# d_main3.net
KiCad netlist of a schematic drawn in EAGLE
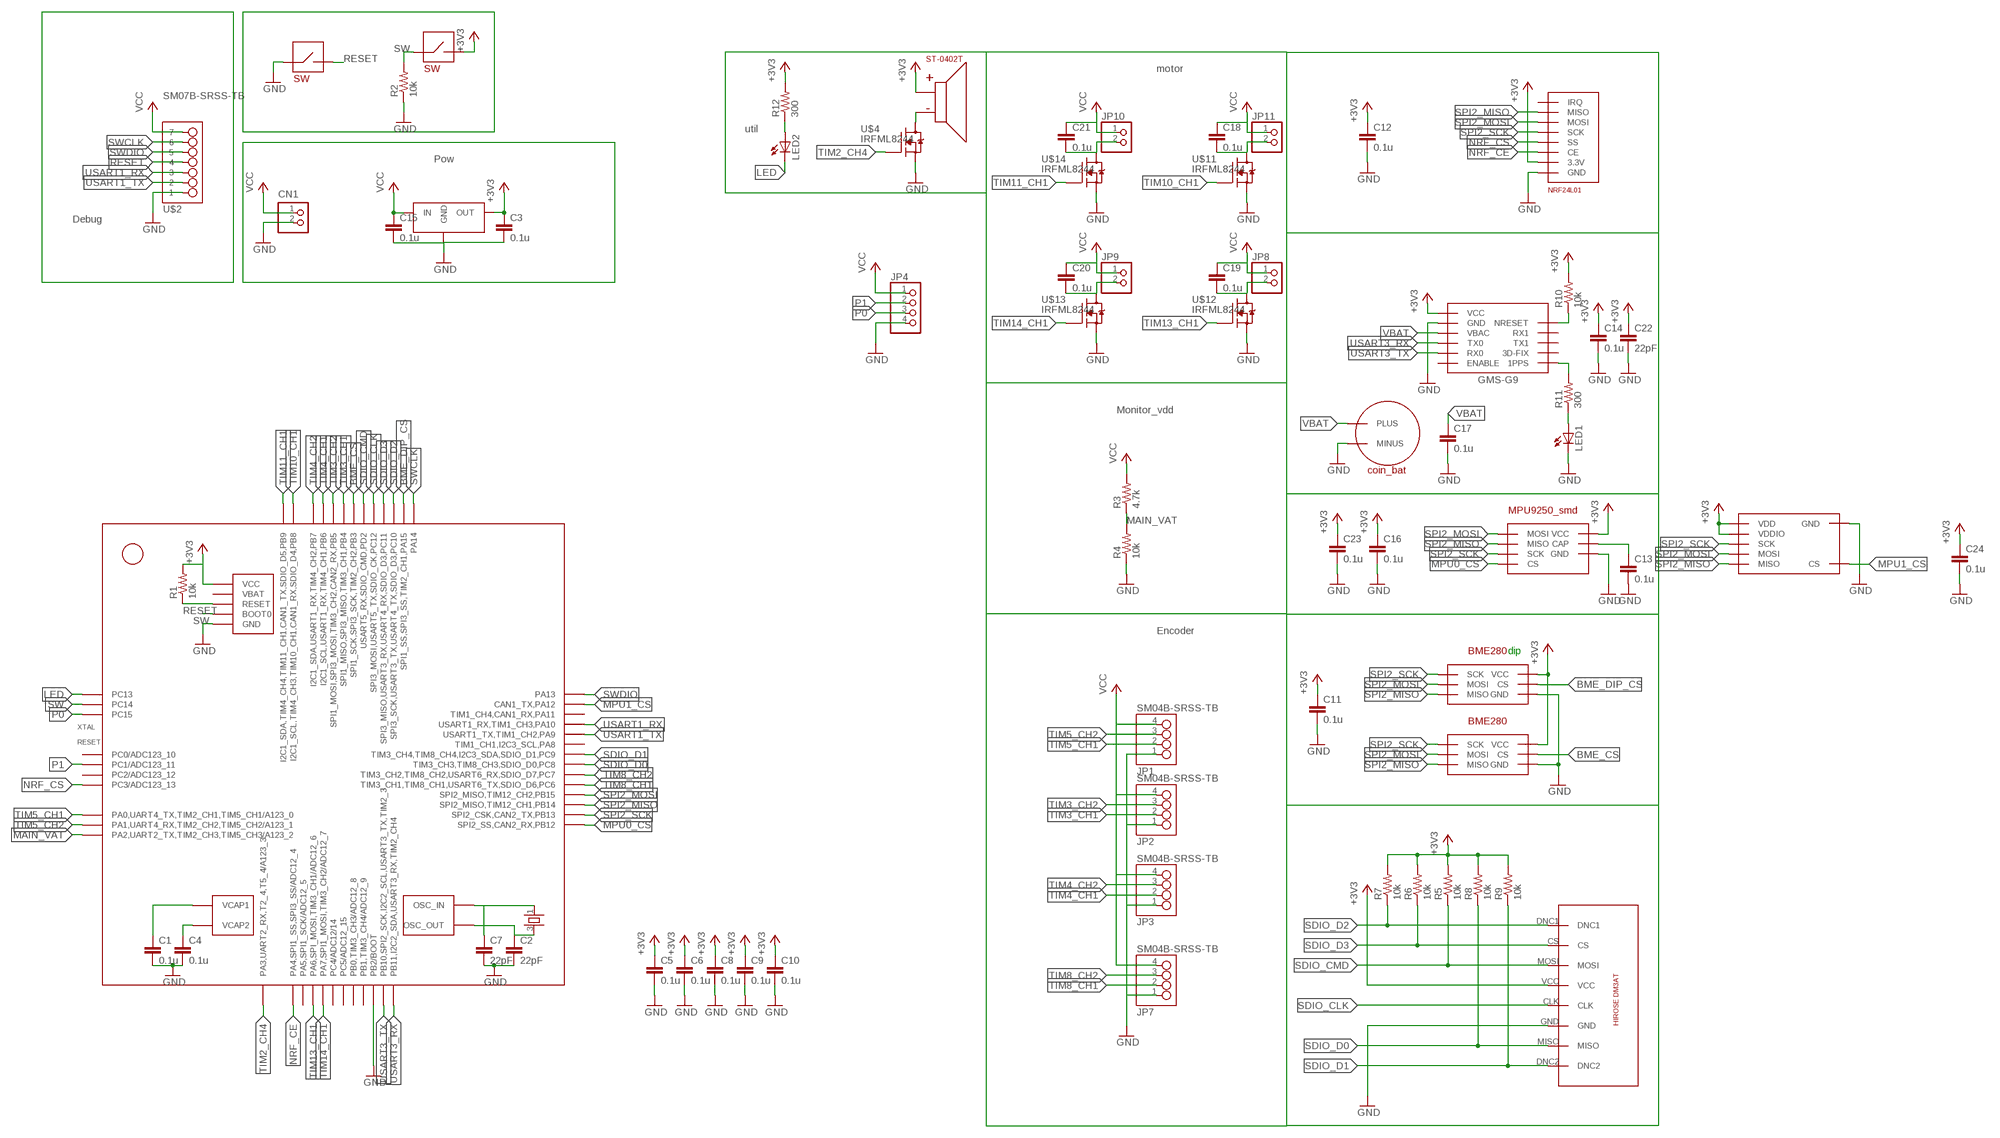
[diagram p0: schematic, sheet 1]

(export (version "E")
  (design (tool "Eeschema 10.0.6"))
  (components
    (comp (ref "C1")
      (value "0.1u")
      (footprint "eagle-import:C0603K")
      (libsource (lib "eagle-import") (part "C-EUC0603K"))
    )
    (comp (ref "C2")
      (value "22pF")
      (footprint "eagle-import:C0603K")
      (libsource (lib "eagle-import") (part "C-EUC0603K"))
    )
    (comp (ref "C3")
      (value "0.1u")
      (footprint "eagle-import:C0603K")
      (libsource (lib "eagle-import") (part "C-EUC0603K"))
    )
    (comp (ref "C4")
      (value "0.1u")
      (footprint "eagle-import:C0603K")
      (libsource (lib "eagle-import") (part "C-EUC0603K"))
    )
    (comp (ref "C5")
      (value "0.1u")
      (footprint "eagle-import:C0603K")
      (libsource (lib "eagle-import") (part "C-EUC0603K"))
    )
    (comp (ref "C6")
      (value "0.1u")
      (footprint "eagle-import:C0603K")
      (libsource (lib "eagle-import") (part "C-EUC0603K"))
    )
    (comp (ref "C7")
      (value "22pF")
      (footprint "eagle-import:C0603K")
      (libsource (lib "eagle-import") (part "C-EUC0603K"))
    )
    (comp (ref "C8")
      (value "0.1u")
      (footprint "eagle-import:C0603K")
      (libsource (lib "eagle-import") (part "C-EUC0603K"))
    )
    (comp (ref "C9")
      (value "0.1u")
      (footprint "eagle-import:C0603K")
      (libsource (lib "eagle-import") (part "C-EUC0603K"))
    )
    (comp (ref "C10")
      (value "0.1u")
      (footprint "eagle-import:C0603K")
      (libsource (lib "eagle-import") (part "C-EUC0603K"))
    )
    (comp (ref "C11")
      (value "0.1u")
      (footprint "eagle-import:C0603K")
      (libsource (lib "eagle-import") (part "C-EUC0603K"))
    )
    (comp (ref "C12")
      (value "0.1u")
      (footprint "eagle-import:C0603K")
      (libsource (lib "eagle-import") (part "C-EUC0603K"))
    )
    (comp (ref "C13")
      (value "0.1u")
      (footprint "eagle-import:C0603K")
      (libsource (lib "eagle-import") (part "C-EUC0603K"))
    )
    (comp (ref "C14")
      (value "0.1u")
      (footprint "eagle-import:C0603K")
      (libsource (lib "eagle-import") (part "C-EUC0603K"))
    )
    (comp (ref "C15")
      (value "0.1u")
      (footprint "eagle-import:C0603K")
      (libsource (lib "eagle-import") (part "C-EUC0603K"))
    )
    (comp (ref "C16")
      (value "0.1u")
      (footprint "eagle-import:C0603K")
      (libsource (lib "eagle-import") (part "C-EUC0603K"))
    )
    (comp (ref "C17")
      (value "0.1u")
      (footprint "eagle-import:C0603K")
      (libsource (lib "eagle-import") (part "C-EUC0603K"))
    )
    (comp (ref "C18")
      (value "0.1u")
      (footprint "eagle-import:C0603K")
      (libsource (lib "eagle-import") (part "C-EUC0603K"))
    )
    (comp (ref "C19")
      (value "0.1u")
      (footprint "eagle-import:C0603K")
      (libsource (lib "eagle-import") (part "C-EUC0603K"))
    )
    (comp (ref "C20")
      (value "0.1u")
      (footprint "eagle-import:C0603K")
      (libsource (lib "eagle-import") (part "C-EUC0603K"))
    )
    (comp (ref "C21")
      (value "0.1u")
      (footprint "eagle-import:C0603K")
      (libsource (lib "eagle-import") (part "C-EUC0603K"))
    )
    (comp (ref "C22")
      (value "22pF")
      (footprint "eagle-import:C0603K")
      (libsource (lib "eagle-import") (part "C-EUC0603K"))
    )
    (comp (ref "C23")
      (value "0.1u")
      (footprint "eagle-import:C0603K")
      (libsource (lib "eagle-import") (part "C-EUC0603K"))
    )
    (comp (ref "C24")
      (value "0.1u")
      (footprint "eagle-import:C0603K")
      (libsource (lib "eagle-import") (part "C-EUC0603K"))
    )
    (comp (ref "CN1")
      (value "S2B-XASK-1")
      (footprint "eagle-import:S2B-XASK-1")
      (libsource (lib "eagle-import") (part "S2B-XASK-1"))
    )
    (comp (ref "JP1")
      (value "SM04B-SRSS-TB")
      (footprint "eagle-import:SM04B-SRSS-TB")
      (libsource (lib "eagle-import") (part "SM04B-SRSS-TB"))
    )
    (comp (ref "JP2")
      (value "SM04B-SRSS-TB")
      (footprint "eagle-import:SM04B-SRSS-TB")
      (libsource (lib "eagle-import") (part "SM04B-SRSS-TB"))
    )
    (comp (ref "JP3")
      (value "SM04B-SRSS-TB")
      (footprint "eagle-import:SM04B-SRSS-TB")
      (libsource (lib "eagle-import") (part "SM04B-SRSS-TB"))
    )
    (comp (ref "JP4")
      (value "PINHD-1X4")
      (footprint "eagle-import:1X04")
      (libsource (lib "eagle-import") (part "PINHD-1X4"))
    )
    (comp (ref "JP7")
      (value "SM04B-SRSS-TB")
      (footprint "eagle-import:SM04B-SRSS-TB")
      (libsource (lib "eagle-import") (part "SM04B-SRSS-TB"))
    )
    (comp (ref "JP8")
      (value "PINHD-1X2")
      (footprint "eagle-import:1X02")
      (libsource (lib "eagle-import") (part "PINHD-1X2"))
    )
    (comp (ref "JP9")
      (value "PINHD-1X2")
      (footprint "eagle-import:1X02")
      (libsource (lib "eagle-import") (part "PINHD-1X2"))
    )
    (comp (ref "JP10")
      (value "PINHD-1X2")
      (footprint "eagle-import:1X02")
      (libsource (lib "eagle-import") (part "PINHD-1X2"))
    )
    (comp (ref "JP11")
      (value "PINHD-1X2")
      (footprint "eagle-import:1X02")
      (libsource (lib "eagle-import") (part "PINHD-1X2"))
    )
    (comp (ref "LED1")
      (value "LEDCHIP-LED0603")
      (footprint "eagle-import:CHIP-LED0603")
      (libsource (lib "eagle-import") (part "LEDCHIP-LED0603"))
    )
    (comp (ref "LED2")
      (value "LEDCHIP-LED0603")
      (footprint "eagle-import:CHIP-LED0603")
      (libsource (lib "eagle-import") (part "LEDCHIP-LED0603"))
    )
    (comp (ref "R1")
      (value "10k")
      (footprint "eagle-import:R0603")
      (libsource (lib "eagle-import") (part "R-US_R0603"))
    )
    (comp (ref "R2")
      (value "10k")
      (footprint "eagle-import:R0603")
      (libsource (lib "eagle-import") (part "R-US_R0603"))
    )
    (comp (ref "R3")
      (value "4.7k")
      (footprint "eagle-import:R0603")
      (libsource (lib "eagle-import") (part "R-US_R0603"))
    )
    (comp (ref "R4")
      (value "10k")
      (footprint "eagle-import:R0603")
      (libsource (lib "eagle-import") (part "R-US_R0603"))
    )
    (comp (ref "R5")
      (value "10k")
      (footprint "eagle-import:R0603")
      (libsource (lib "eagle-import") (part "R-US_R0603"))
    )
    (comp (ref "R6")
      (value "10k")
      (footprint "eagle-import:R0603")
      (libsource (lib "eagle-import") (part "R-US_R0603"))
    )
    (comp (ref "R7")
      (value "10k")
      (footprint "eagle-import:R0603")
      (libsource (lib "eagle-import") (part "R-US_R0603"))
    )
    (comp (ref "R8")
      (value "10k")
      (footprint "eagle-import:R0603")
      (libsource (lib "eagle-import") (part "R-US_R0603"))
    )
    (comp (ref "R9")
      (value "10k")
      (footprint "eagle-import:R0603")
      (libsource (lib "eagle-import") (part "R-US_R0603"))
    )
    (comp (ref "R10")
      (value "10k")
      (footprint "eagle-import:R0603")
      (libsource (lib "eagle-import") (part "R-US_R0603"))
    )
    (comp (ref "R11")
      (value "300")
      (footprint "eagle-import:R0603")
      (libsource (lib "eagle-import") (part "R-US_R0603"))
    )
    (comp (ref "R12")
      (value "300")
      (footprint "eagle-import:R0603")
      (libsource (lib "eagle-import") (part "R-US_R0603"))
    )
    (comp (ref "STM32F405RGT6")
      (value "STM32F405_T")
      (footprint "eagle-import:LQFP64")
      (libsource (lib "eagle-import") (part "STM32F405_T"))
    )
    (comp (ref "U$1")
      (value "GMS-G9")
      (footprint "eagle-import:GMS-G9")
      (libsource (lib "eagle-import") (part "GMS-G9"))
    )
    (comp (ref "U$2")
      (value "SM07B-SRSS-TB")
      (footprint "eagle-import:SM07B-SRSS-TB")
      (libsource (lib "eagle-import") (part "SM07B-SRSS-TB"))
    )
    (comp (ref "U$3")
      (value "NRF24L01")
      (footprint "eagle-import:NRF24L01")
      (libsource (lib "eagle-import") (part "NRF24L01"))
    )
    (comp (ref "U$4")
      (value "IRFML8244")
      (footprint "eagle-import:SOT23")
      (libsource (lib "eagle-import") (part "IRFML8244"))
    )
    (comp (ref "U$5")
      (value "DM3AT")
      (footprint "eagle-import:DM3AT")
      (libsource (lib "eagle-import") (part "DM3AT"))
    )
    (comp (ref "U$6")
      (value "SWTVBP06-B043CB-B")
      (footprint "eagle-import:SW")
      (libsource (lib "eagle-import") (part "SWTVBP06-B043CB-B"))
    )
    (comp (ref "U$7")
      (value "SWTVBP06-B043CB-B")
      (footprint "eagle-import:SW")
      (libsource (lib "eagle-import") (part "SWTVBP06-B043CB-B"))
    )
    (comp (ref "U$8")
      (value "AP7361-33E")
      (footprint "eagle-import:SOT223")
      (libsource (lib "eagle-import") (part "AP7361-33E"))
    )
    (comp (ref "U$9")
      (value "25MHz")
      (footprint "eagle-import:ASF")
      (libsource (lib "eagle-import") (part "ASF_T"))
    )
    (comp (ref "U$10")
      (value "36-3030-ND")
      (footprint "eagle-import:36-3030-ND")
      (libsource (lib "eagle-import") (part "36-3030-ND"))
    )
    (comp (ref "U$11")
      (value "IRFML8244")
      (footprint "eagle-import:SOT23")
      (libsource (lib "eagle-import") (part "IRFML8244"))
    )
    (comp (ref "U$12")
      (value "IRFML8244")
      (footprint "eagle-import:SOT23")
      (libsource (lib "eagle-import") (part "IRFML8244"))
    )
    (comp (ref "U$13")
      (value "IRFML8244")
      (footprint "eagle-import:SOT23")
      (libsource (lib "eagle-import") (part "IRFML8244"))
    )
    (comp (ref "U$14")
      (value "IRFML8244")
      (footprint "eagle-import:SOT23")
      (libsource (lib "eagle-import") (part "IRFML8244"))
    )
    (comp (ref "U$15")
      (value "MPU9250")
      (footprint "eagle-import:MPU9250_DIP")
      (libsource (lib "eagle-import") (part "MPU9250"))
    )
    (comp (ref "U$16")
      (value "MPU9250_SMD")
      (footprint "eagle-import:MPU9250_SMD")
      (libsource (lib "eagle-import") (part "MPU9250_SMD"))
    )
    (comp (ref "U$17")
      (value "BME280")
      (footprint "eagle-import:BME280")
      (libsource (lib "eagle-import") (part "BME280"))
    )
    (comp (ref "U$18")
      (value "ST-0402T")
      (footprint "eagle-import:ST-0402T")
      (libsource (lib "eagle-import") (part "ST-0402T"))
    )
    (comp (ref "U$19")
      (value "BME280_DIP")
      (footprint "eagle-import:BME280_DIP")
      (libsource (lib "eagle-import") (part "BME280_DIP"))
    )
  )
  (nets
    (net (code "1") (name "+3V3") (class "Default")
      (node (ref "C10") (pin "1") (pinfunction "1_1") (pintype "passive"))
      (node (ref "C11") (pin "1") (pinfunction "1_1") (pintype "passive"))
      (node (ref "C12") (pin "1") (pinfunction "1_1") (pintype "passive"))
      (node (ref "C14") (pin "1") (pinfunction "1_1") (pintype "passive"))
      (node (ref "C16") (pin "1") (pinfunction "1_1") (pintype "passive"))
      (node (ref "C22") (pin "1") (pinfunction "1_1") (pintype "passive"))
      (node (ref "C23") (pin "1") (pinfunction "1_1") (pintype "passive"))
      (node (ref "C24") (pin "1") (pinfunction "1_1") (pintype "passive"))
      (node (ref "C3") (pin "1") (pinfunction "1_1") (pintype "passive"))
      (node (ref "C5") (pin "1") (pinfunction "1_1") (pintype "passive"))
      (node (ref "C6") (pin "1") (pinfunction "1_1") (pintype "passive"))
      (node (ref "C8") (pin "1") (pinfunction "1_1") (pintype "passive"))
      (node (ref "C9") (pin "1") (pinfunction "1_1") (pintype "passive"))
      (node (ref "R1") (pin "2") (pinfunction "2_2") (pintype "passive"))
      (node (ref "R10") (pin "2") (pinfunction "2_2") (pintype "passive"))
      (node (ref "R12") (pin "2") (pinfunction "2_2") (pintype "passive"))
      (node (ref "R5") (pin "2") (pinfunction "2_2") (pintype "passive"))
      (node (ref "R6") (pin "2") (pinfunction "2_2") (pintype "passive"))
      (node (ref "R7") (pin "2") (pinfunction "2_2") (pintype "passive"))
      (node (ref "R8") (pin "2") (pinfunction "2_2") (pintype "passive"))
      (node (ref "R9") (pin "2") (pinfunction "2_2") (pintype "passive"))
      (node (ref "STM32F405RGT6") (pin "13") (pinfunction "VCC_13") (pintype "bidirectional"))
      (node (ref "STM32F405RGT6") (pin "19") (pinfunction "VCC_19") (pintype "bidirectional"))
      (node (ref "STM32F405RGT6") (pin "32") (pinfunction "VCC_32") (pintype "bidirectional"))
      (node (ref "STM32F405RGT6") (pin "48") (pinfunction "VCC_48") (pintype "bidirectional"))
      (node (ref "STM32F405RGT6") (pin "64") (pinfunction "VCC_64") (pintype "bidirectional"))
      (node (ref "U$1") (pin "VCC") (pinfunction "VCC_VCC") (pintype "bidirectional"))
      (node (ref "U$15") (pin "VDD") (pinfunction "VDD_VDD") (pintype "bidirectional"))
      (node (ref "U$15") (pin "VDDIO") (pinfunction "VDDIO_VDDIO") (pintype "bidirectional"))
      (node (ref "U$16") (pin "RESV") (pinfunction "VCC_RESV") (pintype "bidirectional"))
      (node (ref "U$16") (pin "VDD") (pinfunction "VCC_VDD") (pintype "bidirectional"))
      (node (ref "U$16") (pin "VDDIO") (pinfunction "VCC_VDDIO") (pintype "bidirectional"))
      (node (ref "U$17") (pin "VDD") (pinfunction "VCC_VDD") (pintype "bidirectional"))
      (node (ref "U$17") (pin "VDDIO") (pinfunction "VCC_VDDIO") (pintype "bidirectional"))
      (node (ref "U$18") (pin "PLUS") (pinfunction "PLUS_PLUS") (pintype "bidirectional"))
      (node (ref "U$19") (pin "VCC") (pinfunction "VCC_VCC") (pintype "bidirectional"))
      (node (ref "U$3") (pin "3.3V") (pinfunction "3.3V_3.3V") (pintype "bidirectional"))
      (node (ref "U$5") (pin "VCC") (pinfunction "VCC_VCC") (pintype "bidirectional"))
      (node (ref "U$7") (pin "P$2") (pinfunction "P$2_P$2") (pintype "bidirectional"))
      (node (ref "U$8") (pin "OUT") (pinfunction "OUT_OUT") (pintype "bidirectional"))
    )
    (net (code "2") (name "BME_CS") (class "Default")
      (node (ref "STM32F405RGT6") (pin "55") (pinfunction "SPI1_SCK,SPI3_SCK,TIM2_CH2,PB3_55") (pintype "bidirectional"))
      (node (ref "U$17") (pin "CS") (pinfunction "CS_CS") (pintype "bidirectional"))
    )
    (net (code "3") (name "BME_DIP_CS") (class "Default")
      (node (ref "STM32F405RGT6") (pin "50") (pinfunction "SPI1_SS,SPI3_SS,TIM2_CH1,PA15_50") (pintype "bidirectional"))
      (node (ref "U$19") (pin "CS") (pinfunction "CS_CS") (pintype "bidirectional"))
    )
    (net (code "4") (name "GND") (class "Default")
      (node (ref "C1") (pin "2") (pinfunction "2_2") (pintype "passive"))
      (node (ref "C10") (pin "2") (pinfunction "2_2") (pintype "passive"))
      (node (ref "C11") (pin "2") (pinfunction "2_2") (pintype "passive"))
      (node (ref "C12") (pin "2") (pinfunction "2_2") (pintype "passive"))
      (node (ref "C13") (pin "2") (pinfunction "2_2") (pintype "passive"))
      (node (ref "C14") (pin "2") (pinfunction "2_2") (pintype "passive"))
      (node (ref "C15") (pin "2") (pinfunction "2_2") (pintype "passive"))
      (node (ref "C16") (pin "2") (pinfunction "2_2") (pintype "passive"))
      (node (ref "C17") (pin "2") (pinfunction "2_2") (pintype "passive"))
      (node (ref "C2") (pin "2") (pinfunction "2_2") (pintype "passive"))
      (node (ref "C22") (pin "2") (pinfunction "2_2") (pintype "passive"))
      (node (ref "C23") (pin "2") (pinfunction "2_2") (pintype "passive"))
      (node (ref "C24") (pin "2") (pinfunction "2_2") (pintype "passive"))
      (node (ref "C3") (pin "2") (pinfunction "2_2") (pintype "passive"))
      (node (ref "C4") (pin "2") (pinfunction "2_2") (pintype "passive"))
      (node (ref "C5") (pin "2") (pinfunction "2_2") (pintype "passive"))
      (node (ref "C6") (pin "2") (pinfunction "2_2") (pintype "passive"))
      (node (ref "C7") (pin "2") (pinfunction "2_2") (pintype "passive"))
      (node (ref "C8") (pin "2") (pinfunction "2_2") (pintype "passive"))
      (node (ref "C9") (pin "2") (pinfunction "2_2") (pintype "passive"))
      (node (ref "CN1") (pin "2") (pinfunction "2_2") (pintype "passive"))
      (node (ref "JP1") (pin "1") (pinfunction "P$1_1") (pintype "bidirectional"))
      (node (ref "JP2") (pin "1") (pinfunction "P$1_1") (pintype "bidirectional"))
      (node (ref "JP3") (pin "1") (pinfunction "P$1_1") (pintype "bidirectional"))
      (node (ref "JP4") (pin "4") (pinfunction "4_4") (pintype "passive"))
      (node (ref "JP7") (pin "1") (pinfunction "P$1_1") (pintype "bidirectional"))
      (node (ref "LED1") (pin "C") (pinfunction "C_C") (pintype "passive"))
      (node (ref "R2") (pin "1") (pinfunction "1_1") (pintype "passive"))
      (node (ref "R4") (pin "1") (pinfunction "1_1") (pintype "passive"))
      (node (ref "STM32F405RGT6") (pin "12") (pinfunction "GND_12") (pintype "bidirectional"))
      (node (ref "STM32F405RGT6") (pin "18") (pinfunction "GND_18") (pintype "bidirectional"))
      (node (ref "STM32F405RGT6") (pin "28") (pinfunction "PB2/BOOT_28") (pintype "bidirectional"))
      (node (ref "STM32F405RGT6") (pin "63") (pinfunction "GND_63") (pintype "bidirectional"))
      (node (ref "U$1") (pin "GND") (pinfunction "GND_GND") (pintype "bidirectional"))
      (node (ref "U$1") (pin "GND1") (pinfunction "GND_GND1") (pintype "bidirectional"))
      (node (ref "U$10") (pin "MINUS") (pinfunction "MINUS_MINUS") (pintype "bidirectional"))
      (node (ref "U$11") (pin "2") (pinfunction "S_2") (pintype "passive"))
      (node (ref "U$12") (pin "2") (pinfunction "S_2") (pintype "passive"))
      (node (ref "U$13") (pin "2") (pinfunction "S_2") (pintype "passive"))
      (node (ref "U$14") (pin "2") (pinfunction "S_2") (pintype "passive"))
      (node (ref "U$15") (pin "GND") (pinfunction "GND_GND") (pintype "bidirectional"))
      (node (ref "U$16") (pin "GND") (pinfunction "GND_GND") (pintype "bidirectional"))
      (node (ref "U$16") (pin "~RESV") (pinfunction "GND_~RESV") (pintype "bidirectional"))
      (node (ref "U$17") (pin "GND") (pinfunction "GND_GND") (pintype "bidirectional"))
      (node (ref "U$17") (pin "GND1") (pinfunction "GND_GND1") (pintype "bidirectional"))
      (node (ref "U$19") (pin "GND") (pinfunction "GND_GND") (pintype "bidirectional"))
      (node (ref "U$2") (pin "P$1") (pinfunction "1_P$1") (pintype "bidirectional"))
      (node (ref "U$3") (pin "GND") (pinfunction "GND_GND") (pintype "bidirectional"))
      (node (ref "U$4") (pin "2") (pinfunction "S_2") (pintype "passive"))
      (node (ref "U$5") (pin "GND") (pinfunction "GND_GND") (pintype "bidirectional"))
      (node (ref "U$6") (pin "P$1") (pinfunction "P$1_P$1") (pintype "bidirectional"))
      (node (ref "U$8") (pin "GND1") (pinfunction "GND_GND1") (pintype "bidirectional"))
      (node (ref "U$8") (pin "GND2") (pinfunction "GND_GND2") (pintype "bidirectional"))
    )
    (net (code "5") (name "LED") (class "Default")
      (node (ref "LED2") (pin "C") (pinfunction "C_C") (pintype "passive"))
      (node (ref "STM32F405RGT6") (pin "2") (pinfunction "PC13_2") (pintype "bidirectional"))
    )
    (net (code "6") (name "MAIN_VAT") (class "Default")
      (node (ref "R3") (pin "1") (pinfunction "1_1") (pintype "passive"))
      (node (ref "R4") (pin "2") (pinfunction "2_2") (pintype "passive"))
      (node (ref "STM32F405RGT6") (pin "16") (pinfunction "PA2,UART2_TX,TIM2_CH3,TIM5_CH3/A123_2_16") (pintype "bidirectional"))
    )
    (net (code "7") (name "MPU0_CS") (class "Default")
      (node (ref "STM32F405RGT6") (pin "33") (pinfunction "SPI2_SS,CAN2_RX,PB12_33") (pintype "bidirectional"))
      (node (ref "U$16") (pin "CS") (pinfunction "CS_CS") (pintype "bidirectional"))
    )
    (net (code "8") (name "MPU1_CS") (class "Default")
      (node (ref "STM32F405RGT6") (pin "45") (pinfunction "CAN1_TX,PA12_45") (pintype "bidirectional"))
      (node (ref "U$15") (pin "CS") (pinfunction "CS_CS") (pintype "bidirectional"))
    )
    (net (code "9") (name "NRF_CE") (class "Default")
      (node (ref "STM32F405RGT6") (pin "20") (pinfunction "PA4,SPI1_SS,SPI3_SS/ADC12_4_20") (pintype "bidirectional"))
      (node (ref "U$3") (pin "CE") (pinfunction "CE_CE") (pintype "bidirectional"))
    )
    (net (code "10") (name "NRF_CS") (class "Default")
      (node (ref "STM32F405RGT6") (pin "11") (pinfunction "PC3/ADC123_13_11") (pintype "bidirectional"))
      (node (ref "U$3") (pin "SS") (pinfunction "SS_SS") (pintype "bidirectional"))
    )
    (net (code "11") (name "Net-(LED1-PadA)") (class "Default")
      (node (ref "LED1") (pin "A") (pinfunction "A_A") (pintype "passive"))
      (node (ref "R11") (pin "1") (pinfunction "1_1") (pintype "passive"))
    )
    (net (code "12") (name "Net-(LED2-PadA)") (class "Default")
      (node (ref "LED2") (pin "A") (pinfunction "A_A") (pintype "passive"))
      (node (ref "R12") (pin "1") (pinfunction "1_1") (pintype "passive"))
    )
    (net (code "13") (name "Net-(R10-Pad1)") (class "Default")
      (node (ref "R10") (pin "1") (pinfunction "1_1") (pintype "passive"))
      (node (ref "U$1") (pin "NRESET") (pinfunction "NRESET_NRESET") (pintype "bidirectional"))
    )
    (net (code "14") (name "Net-(R11-Pad2)") (class "Default")
      (node (ref "R11") (pin "2") (pinfunction "2_2") (pintype "passive"))
      (node (ref "U$1") (pin "1PPS") (pinfunction "1PPS_1PPS") (pintype "bidirectional"))
    )
    (net (code "15") (name "Net-(STM32F405RGT6-OSC_IN)") (class "Default")
      (node (ref "C7") (pin "1") (pinfunction "1_1") (pintype "passive"))
      (node (ref "STM32F405RGT6") (pin "5") (pinfunction "OSC_IN_5") (pintype "bidirectional"))
      (node (ref "U$9") (pin "1") (pinfunction "P$1_1") (pintype "bidirectional"))
    )
    (net (code "16") (name "Net-(STM32F405RGT6-OSC_OUT)") (class "Default")
      (node (ref "C2") (pin "1") (pinfunction "1_1") (pintype "passive"))
      (node (ref "STM32F405RGT6") (pin "6") (pinfunction "OSC_OUT_6") (pintype "bidirectional"))
      (node (ref "U$9") (pin "3") (pinfunction "P$2_3") (pintype "bidirectional"))
    )
    (net (code "17") (name "Net-(STM32F405RGT6-VCAP1)") (class "Default")
      (node (ref "C1") (pin "1") (pinfunction "1_1") (pintype "passive"))
      (node (ref "STM32F405RGT6") (pin "31") (pinfunction "VCAP1_31") (pintype "bidirectional"))
    )
    (net (code "18") (name "Net-(STM32F405RGT6-VCAP2)") (class "Default")
      (node (ref "C4") (pin "1") (pinfunction "1_1") (pintype "passive"))
      (node (ref "STM32F405RGT6") (pin "47") (pinfunction "VCAP2_47") (pintype "bidirectional"))
    )
    (net (code "19") (name "Net-(U$4-D)") (class "Default")
      (node (ref "U$18") (pin "MINUS") (pinfunction "MINUS_MINUS") (pintype "bidirectional"))
      (node (ref "U$4") (pin "3") (pinfunction "D_3") (pintype "passive"))
    )
    (net (code "20") (name "Net-(U$11-D)") (class "Default")
      (node (ref "C18") (pin "2") (pinfunction "2_2") (pintype "passive"))
      (node (ref "JP11") (pin "2") (pinfunction "2_2") (pintype "passive"))
      (node (ref "U$11") (pin "3") (pinfunction "D_3") (pintype "passive"))
    )
    (net (code "21") (name "Net-(U$12-D)") (class "Default")
      (node (ref "C19") (pin "2") (pinfunction "2_2") (pintype "passive"))
      (node (ref "JP8") (pin "2") (pinfunction "2_2") (pintype "passive"))
      (node (ref "U$12") (pin "3") (pinfunction "D_3") (pintype "passive"))
    )
    (net (code "22") (name "Net-(U$13-D)") (class "Default")
      (node (ref "C20") (pin "2") (pinfunction "2_2") (pintype "passive"))
      (node (ref "JP9") (pin "2") (pinfunction "2_2") (pintype "passive"))
      (node (ref "U$13") (pin "3") (pinfunction "D_3") (pintype "passive"))
    )
    (net (code "23") (name "Net-(U$14-D)") (class "Default")
      (node (ref "C21") (pin "2") (pinfunction "2_2") (pintype "passive"))
      (node (ref "JP10") (pin "2") (pinfunction "2_2") (pintype "passive"))
      (node (ref "U$14") (pin "3") (pinfunction "D_3") (pintype "passive"))
    )
    (net (code "24") (name "Net-(U$16-CAP)") (class "Default")
      (node (ref "C13") (pin "1") (pinfunction "1_1") (pintype "passive"))
      (node (ref "U$16") (pin "REGOUT") (pinfunction "CAP_REGOUT") (pintype "bidirectional"))
    )
    (net (code "25") (name "P0") (class "Default")
      (node (ref "JP4") (pin "3") (pinfunction "3_3") (pintype "passive"))
      (node (ref "STM32F405RGT6") (pin "4") (pinfunction "PC15_4") (pintype "bidirectional"))
    )
    (net (code "26") (name "P1") (class "Default")
      (node (ref "JP4") (pin "2") (pinfunction "2_2") (pintype "passive"))
      (node (ref "STM32F405RGT6") (pin "9") (pinfunction "PC1/ADC123_11_9") (pintype "bidirectional"))
    )
    (net (code "27") (name "RESET") (class "Default")
      (node (ref "R1") (pin "1") (pinfunction "1_1") (pintype "passive"))
      (node (ref "STM32F405RGT6") (pin "7") (pinfunction "RESET_7") (pintype "bidirectional"))
      (node (ref "U$2") (pin "P$4") (pinfunction "4_P$4") (pintype "bidirectional"))
      (node (ref "U$6") (pin "P$2") (pinfunction "P$2_P$2") (pintype "bidirectional"))
    )
    (net (code "28") (name "SDIO_CLK") (class "Default")
      (node (ref "STM32F405RGT6") (pin "53") (pinfunction "SPI3_MOSI,USART5_TX,SDIO_CK,PC12_53") (pintype "bidirectional"))
      (node (ref "U$5") (pin "CLK") (pinfunction "CLK_CLK") (pintype "bidirectional"))
    )
    (net (code "29") (name "SDIO_CMD") (class "Default")
      (node (ref "R5") (pin "1") (pinfunction "1_1") (pintype "passive"))
      (node (ref "STM32F405RGT6") (pin "54") (pinfunction "USART5_RX,SDIO_CMD,PD2_54") (pintype "bidirectional"))
      (node (ref "U$5") (pin "MOSI") (pinfunction "MOSI_MOSI") (pintype "bidirectional"))
    )
    (net (code "30") (name "SDIO_D0") (class "Default")
      (node (ref "R8") (pin "1") (pinfunction "1_1") (pintype "passive"))
      (node (ref "STM32F405RGT6") (pin "39") (pinfunction "TIM3_CH3,TIM8_CH3,SDIO_D0,PC8_39") (pintype "bidirectional"))
      (node (ref "U$5") (pin "MISO") (pinfunction "MISO_MISO") (pintype "bidirectional"))
    )
    (net (code "31") (name "SDIO_D1") (class "Default")
      (node (ref "R9") (pin "1") (pinfunction "1_1") (pintype "passive"))
      (node (ref "STM32F405RGT6") (pin "40") (pinfunction "TIM3_CH4,TIM8_CH4,I2C3_SDA,SDIO_D1,PC9_40") (pintype "bidirectional"))
      (node (ref "U$5") (pin "DNC2") (pinfunction "DNC2_DNC2") (pintype "bidirectional"))
    )
    (net (code "32") (name "SDIO_D2") (class "Default")
      (node (ref "R7") (pin "1") (pinfunction "1_1") (pintype "passive"))
      (node (ref "STM32F405RGT6") (pin "51") (pinfunction "SPI3_SCK,USART3_TX,USART4_TX,SDIO_D3,PC10_51") (pintype "bidirectional"))
      (node (ref "U$5") (pin "DNC1") (pinfunction "DNC1_DNC1") (pintype "bidirectional"))
    )
    (net (code "33") (name "SDIO_D3") (class "Default")
      (node (ref "R6") (pin "1") (pinfunction "1_1") (pintype "passive"))
      (node (ref "STM32F405RGT6") (pin "52") (pinfunction "SPI3_MISO,USART3_RX,USART4_RX,SDIO_D3,PC11_52") (pintype "bidirectional"))
      (node (ref "U$5") (pin "CS") (pinfunction "CS_CS") (pintype "bidirectional"))
    )
    (net (code "34") (name "SPI2_MISO") (class "Default")
      (node (ref "STM32F405RGT6") (pin "35") (pinfunction "SPI2_MISO,TIM12_CH1,PB14_35") (pintype "bidirectional"))
      (node (ref "U$15") (pin "MISO") (pinfunction "MISO_MISO") (pintype "bidirectional"))
      (node (ref "U$16") (pin "MISO") (pinfunction "MISO_MISO") (pintype "bidirectional"))
      (node (ref "U$17") (pin "MISO") (pinfunction "MISO_MISO") (pintype "bidirectional"))
      (node (ref "U$19") (pin "MISO") (pinfunction "MISO_MISO") (pintype "bidirectional"))
      (node (ref "U$3") (pin "MISO") (pinfunction "MISO_MISO") (pintype "bidirectional"))
    )
    (net (code "35") (name "SPI2_MOSI") (class "Default")
      (node (ref "STM32F405RGT6") (pin "36") (pinfunction "SPI2_MISO,TIM12_CH2,PB15_36") (pintype "bidirectional"))
      (node (ref "U$15") (pin "MOSI") (pinfunction "MOSI_MOSI") (pintype "bidirectional"))
      (node (ref "U$16") (pin "MOSI") (pinfunction "MOSI_MOSI") (pintype "bidirectional"))
      (node (ref "U$17") (pin "MOSI") (pinfunction "MOSI_MOSI") (pintype "bidirectional"))
      (node (ref "U$19") (pin "MOSI") (pinfunction "MOSI_MOSI") (pintype "bidirectional"))
      (node (ref "U$3") (pin "MOSI") (pinfunction "MOSI_MOSI") (pintype "bidirectional"))
    )
    (net (code "36") (name "SPI2_SCK") (class "Default")
      (node (ref "STM32F405RGT6") (pin "34") (pinfunction "SPI2_CSK,CAN2_TX,PB13_34") (pintype "bidirectional"))
      (node (ref "U$15") (pin "SCL") (pinfunction "SCK_SCL") (pintype "bidirectional"))
      (node (ref "U$16") (pin "SCK") (pinfunction "SCK_SCK") (pintype "bidirectional"))
      (node (ref "U$17") (pin "SCK") (pinfunction "SCK_SCK") (pintype "bidirectional"))
      (node (ref "U$19") (pin "SCK") (pinfunction "SCK_SCK") (pintype "bidirectional"))
      (node (ref "U$3") (pin "SCK") (pinfunction "SCK_SCK") (pintype "bidirectional"))
    )
    (net (code "37") (name "SW") (class "Default")
      (node (ref "R2") (pin "2") (pinfunction "2_2") (pintype "passive"))
      (node (ref "STM32F405RGT6") (pin "3") (pinfunction "PC14_3") (pintype "bidirectional"))
      (node (ref "STM32F405RGT6") (pin "60") (pinfunction "BOOT0_60") (pintype "bidirectional"))
      (node (ref "U$7") (pin "P$1") (pinfunction "P$1_P$1") (pintype "bidirectional"))
    )
    (net (code "38") (name "SWCLK") (class "Default")
      (node (ref "STM32F405RGT6") (pin "49") (pinfunction "PA14_49") (pintype "bidirectional"))
      (node (ref "U$2") (pin "P$6") (pinfunction "6_P$6") (pintype "bidirectional"))
    )
    (net (code "39") (name "SWDIO") (class "Default")
      (node (ref "STM32F405RGT6") (pin "46") (pinfunction "PA13_46") (pintype "bidirectional"))
      (node (ref "U$2") (pin "P$5") (pinfunction "5_P$5") (pintype "bidirectional"))
    )
    (net (code "40") (name "TIM2_CH4") (class "Default")
      (node (ref "STM32F405RGT6") (pin "17") (pinfunction "PA3,UART2_RX,T2_4,T5_4/A123_3_17") (pintype "bidirectional"))
      (node (ref "U$4") (pin "1") (pinfunction "G_1") (pintype "passive"))
    )
    (net (code "41") (name "TIM3_CH1") (class "Default")
      (node (ref "JP2") (pin "2") (pinfunction "P$2_2") (pintype "bidirectional"))
      (node (ref "STM32F405RGT6") (pin "56") (pinfunction "SPI1_MISO,SPI3_MISO,TIM3_CH1,PB4_56") (pintype "bidirectional"))
    )
    (net (code "42") (name "TIM3_CH2") (class "Default")
      (node (ref "JP2") (pin "3") (pinfunction "P$3_3") (pintype "bidirectional"))
      (node (ref "STM32F405RGT6") (pin "57") (pinfunction "SPI1_MOSI,SPI3_MOSI,TIM3_CH2,CAN2_RX,PB5_57") (pintype "bidirectional"))
    )
    (net (code "43") (name "TIM4_CH1") (class "Default")
      (node (ref "JP3") (pin "2") (pinfunction "P$2_2") (pintype "bidirectional"))
      (node (ref "STM32F405RGT6") (pin "58") (pinfunction "I2C1_SCL,USART1_RX,TIM4_CH1,PB6_58") (pintype "bidirectional"))
    )
    (net (code "44") (name "TIM4_CH2") (class "Default")
      (node (ref "JP3") (pin "3") (pinfunction "P$3_3") (pintype "bidirectional"))
      (node (ref "STM32F405RGT6") (pin "59") (pinfunction "I2C1_SDA,USART1_RX,TIM4_CH2,PB7_59") (pintype "bidirectional"))
    )
    (net (code "45") (name "TIM5_CH1") (class "Default")
      (node (ref "JP1") (pin "2") (pinfunction "P$2_2") (pintype "bidirectional"))
      (node (ref "STM32F405RGT6") (pin "14") (pinfunction "PA0,UART4_TX,TIM2_CH1,TIM5_CH1/A123_0_14") (pintype "bidirectional"))
    )
    (net (code "46") (name "TIM5_CH2") (class "Default")
      (node (ref "JP1") (pin "3") (pinfunction "P$3_3") (pintype "bidirectional"))
      (node (ref "STM32F405RGT6") (pin "15") (pinfunction "PA1,UART4_RX,TIM2_CH2,TIM5_CH2/A123_1_15") (pintype "bidirectional"))
    )
    (net (code "47") (name "TIM8_CH1") (class "Default")
      (node (ref "JP7") (pin "2") (pinfunction "P$2_2") (pintype "bidirectional"))
      (node (ref "STM32F405RGT6") (pin "37") (pinfunction "TIM3_CH1,TIM8_CH1,USART6_TX,SDIO_D6,PC6_37") (pintype "bidirectional"))
    )
    (net (code "48") (name "TIM8_CH2") (class "Default")
      (node (ref "JP7") (pin "3") (pinfunction "P$3_3") (pintype "bidirectional"))
      (node (ref "STM32F405RGT6") (pin "38") (pinfunction "TIM3_CH2,TIM8_CH2,USART6_RX,SDIO_D7,PC7_38") (pintype "bidirectional"))
    )
    (net (code "49") (name "TIM10_CH1") (class "Default")
      (node (ref "STM32F405RGT6") (pin "61") (pinfunction "I2C1_SCL,TIM4_CH3,TIM10_CH1,CAN1_RX,SDIO_D4,PB8_61") (pintype "bidirectional"))
      (node (ref "U$11") (pin "1") (pinfunction "G_1") (pintype "passive"))
    )
    (net (code "50") (name "TIM11_CH1") (class "Default")
      (node (ref "STM32F405RGT6") (pin "62") (pinfunction "I2C1_SDA,TIM4_CH4,TIM11_CH1,CAN1_TX,SDIO_D5,PB9_62") (pintype "bidirectional"))
      (node (ref "U$14") (pin "1") (pinfunction "G_1") (pintype "passive"))
    )
    (net (code "51") (name "TIM13_CH1") (class "Default")
      (node (ref "STM32F405RGT6") (pin "22") (pinfunction "PA6,SPI_MOSI,TIM3_CH1/ADC12_6_22") (pintype "bidirectional"))
      (node (ref "U$12") (pin "1") (pinfunction "G_1") (pintype "passive"))
    )
    (net (code "52") (name "TIM14_CH1") (class "Default")
      (node (ref "STM32F405RGT6") (pin "23") (pinfunction "PA7,SPI1_MOSI,TIM3_CH2/ADC12_7_23") (pintype "bidirectional"))
      (node (ref "U$13") (pin "1") (pinfunction "G_1") (pintype "passive"))
    )
    (net (code "53") (name "USART1_RX") (class "Default")
      (node (ref "STM32F405RGT6") (pin "43") (pinfunction "USART1_RX,TIM1_CH3,PA10_43") (pintype "bidirectional"))
      (node (ref "U$2") (pin "P$3") (pinfunction "3_P$3") (pintype "bidirectional"))
    )
    (net (code "54") (name "USART1_TX") (class "Default")
      (node (ref "STM32F405RGT6") (pin "42") (pinfunction "USART1_TX,TIM1_CH2,PA9_42") (pintype "bidirectional"))
      (node (ref "U$2") (pin "P$2") (pinfunction "2_P$2") (pintype "bidirectional"))
    )
    (net (code "55") (name "USART3_RX") (class "Default")
      (node (ref "STM32F405RGT6") (pin "30") (pinfunction "PB11,I2C2_SDA,USART3_RX,TIM2_CH4_30") (pintype "bidirectional"))
      (node (ref "U$1") (pin "TX0") (pinfunction "TX0_TX0") (pintype "bidirectional"))
    )
    (net (code "56") (name "USART3_TX") (class "Default")
      (node (ref "STM32F405RGT6") (pin "29") (pinfunction "PB10,SPI2_SCK,I2C2_SCL,USART3_TX,TIM2_3_29") (pintype "bidirectional"))
      (node (ref "U$1") (pin "RX0") (pinfunction "RX0_RX0") (pintype "bidirectional"))
    )
    (net (code "57") (name "VBAT") (class "Default")
      (node (ref "C17") (pin "1") (pinfunction "1_1") (pintype "passive"))
      (node (ref "U$1") (pin "VBAC") (pinfunction "VBAC_VBAC") (pintype "bidirectional"))
      (node (ref "U$10") (pin "PLUS1") (pinfunction "PLUS_PLUS1") (pintype "bidirectional"))
      (node (ref "U$10") (pin "PLUS2") (pinfunction "PLUS_PLUS2") (pintype "bidirectional"))
    )
    (net (code "58") (name "VCC") (class "Default")
      (node (ref "C15") (pin "1") (pinfunction "1_1") (pintype "passive"))
      (node (ref "C18") (pin "1") (pinfunction "1_1") (pintype "passive"))
      (node (ref "C19") (pin "1") (pinfunction "1_1") (pintype "passive"))
      (node (ref "C20") (pin "1") (pinfunction "1_1") (pintype "passive"))
      (node (ref "C21") (pin "1") (pinfunction "1_1") (pintype "passive"))
      (node (ref "CN1") (pin "1") (pinfunction "1_1") (pintype "passive"))
      (node (ref "JP1") (pin "4") (pinfunction "P$4_4") (pintype "bidirectional"))
      (node (ref "JP10") (pin "1") (pinfunction "1_1") (pintype "passive"))
      (node (ref "JP11") (pin "1") (pinfunction "1_1") (pintype "passive"))
      (node (ref "JP2") (pin "4") (pinfunction "P$4_4") (pintype "bidirectional"))
      (node (ref "JP3") (pin "4") (pinfunction "P$4_4") (pintype "bidirectional"))
      (node (ref "JP4") (pin "1") (pinfunction "1_1") (pintype "passive"))
      (node (ref "JP7") (pin "4") (pinfunction "P$4_4") (pintype "bidirectional"))
      (node (ref "JP8") (pin "1") (pinfunction "1_1") (pintype "passive"))
      (node (ref "JP9") (pin "1") (pinfunction "1_1") (pintype "passive"))
      (node (ref "R3") (pin "2") (pinfunction "2_2") (pintype "passive"))
      (node (ref "U$2") (pin "P$7") (pinfunction "7_P$7") (pintype "bidirectional"))
      (node (ref "U$8") (pin "IN") (pinfunction "IN_IN") (pintype "bidirectional"))
    )
    (net (code "59") (name "unconnected-(STM32F405RGT6-PA5,SPI1_SCK{slash}ADC12_5-Pad21)") (class "Default")
      (node (ref "STM32F405RGT6") (pin "21") (pinfunction "PA5,SPI1_SCK/ADC12_5_21") (pintype "bidirectional"))
    )
    (net (code "60") (name "unconnected-(STM32F405RGT6-PB0,TIM3_CH3{slash}ADC12_8-Pad26)") (class "Default")
      (node (ref "STM32F405RGT6") (pin "26") (pinfunction "PB0,TIM3_CH3/ADC12_8_26") (pintype "bidirectional"))
    )
    (net (code "61") (name "unconnected-(STM32F405RGT6-PB1,TIM3_CH4{slash}ADC12_9-Pad27)") (class "Default")
      (node (ref "STM32F405RGT6") (pin "27") (pinfunction "PB1,TIM3_CH4/ADC12_9_27") (pintype "bidirectional"))
    )
    (net (code "62") (name "unconnected-(STM32F405RGT6-PC0{slash}ADC123_10-Pad8)") (class "Default")
      (node (ref "STM32F405RGT6") (pin "8") (pinfunction "PC0/ADC123_10_8") (pintype "bidirectional"))
    )
    (net (code "63") (name "unconnected-(STM32F405RGT6-PC2{slash}ADC123_12-Pad10)") (class "Default")
      (node (ref "STM32F405RGT6") (pin "10") (pinfunction "PC2/ADC123_12_10") (pintype "bidirectional"))
    )
    (net (code "64") (name "unconnected-(STM32F405RGT6-PC4{slash}ADC12{slash}14-Pad24)") (class "Default")
      (node (ref "STM32F405RGT6") (pin "24") (pinfunction "PC4/ADC12/14_24") (pintype "bidirectional"))
    )
    (net (code "65") (name "unconnected-(STM32F405RGT6-PC5{slash}ADC12_15-Pad25)") (class "Default")
      (node (ref "STM32F405RGT6") (pin "25") (pinfunction "PC5/ADC12_15_25") (pintype "bidirectional"))
    )
    (net (code "66") (name "unconnected-(STM32F405RGT6-TIM1_CH1,I2C3_SCL,PA8-Pad41)") (class "Default")
      (node (ref "STM32F405RGT6") (pin "41") (pinfunction "TIM1_CH1,I2C3_SCL,PA8_41") (pintype "bidirectional"))
    )
    (net (code "67") (name "unconnected-(STM32F405RGT6-TIM1_CH4,CAN1_RX,PA11-Pad44)") (class "Default")
      (node (ref "STM32F405RGT6") (pin "44") (pinfunction "TIM1_CH4,CAN1_RX,PA11_44") (pintype "bidirectional"))
    )
    (net (code "68") (name "unconnected-(STM32F405RGT6-VBAT-Pad1)") (class "Default")
      (node (ref "STM32F405RGT6") (pin "1") (pinfunction "VBAT_1") (pintype "bidirectional"))
    )
    (net (code "69") (name "unconnected-(U$1-Pad3D-FIX)") (class "Default")
      (node (ref "U$1") (pin "3D-FIX") (pinfunction "3D-FIX_3D-FIX") (pintype "bidirectional"))
    )
    (net (code "70") (name "unconnected-(U$1-PadENABLE)") (class "Default")
      (node (ref "U$1") (pin "ENABLE") (pinfunction "ENABLE_ENABLE") (pintype "bidirectional"))
    )
    (net (code "71") (name "unconnected-(U$1-PadRX1)") (class "Default")
      (node (ref "U$1") (pin "RX1") (pinfunction "RX1_RX1") (pintype "bidirectional"))
    )
    (net (code "72") (name "unconnected-(U$1-PadTX1)") (class "Default")
      (node (ref "U$1") (pin "TX1") (pinfunction "TX1_TX1") (pintype "bidirectional"))
    )
    (net (code "73") (name "unconnected-(U$3-PadIRQ)") (class "Default")
      (node (ref "U$3") (pin "IRQ") (pinfunction "IRQ_IRQ") (pintype "bidirectional"))
    )
  )
)
